# BUTTON-LEDs.net
KiCad netlist of a schematic drawn in Altium Designer
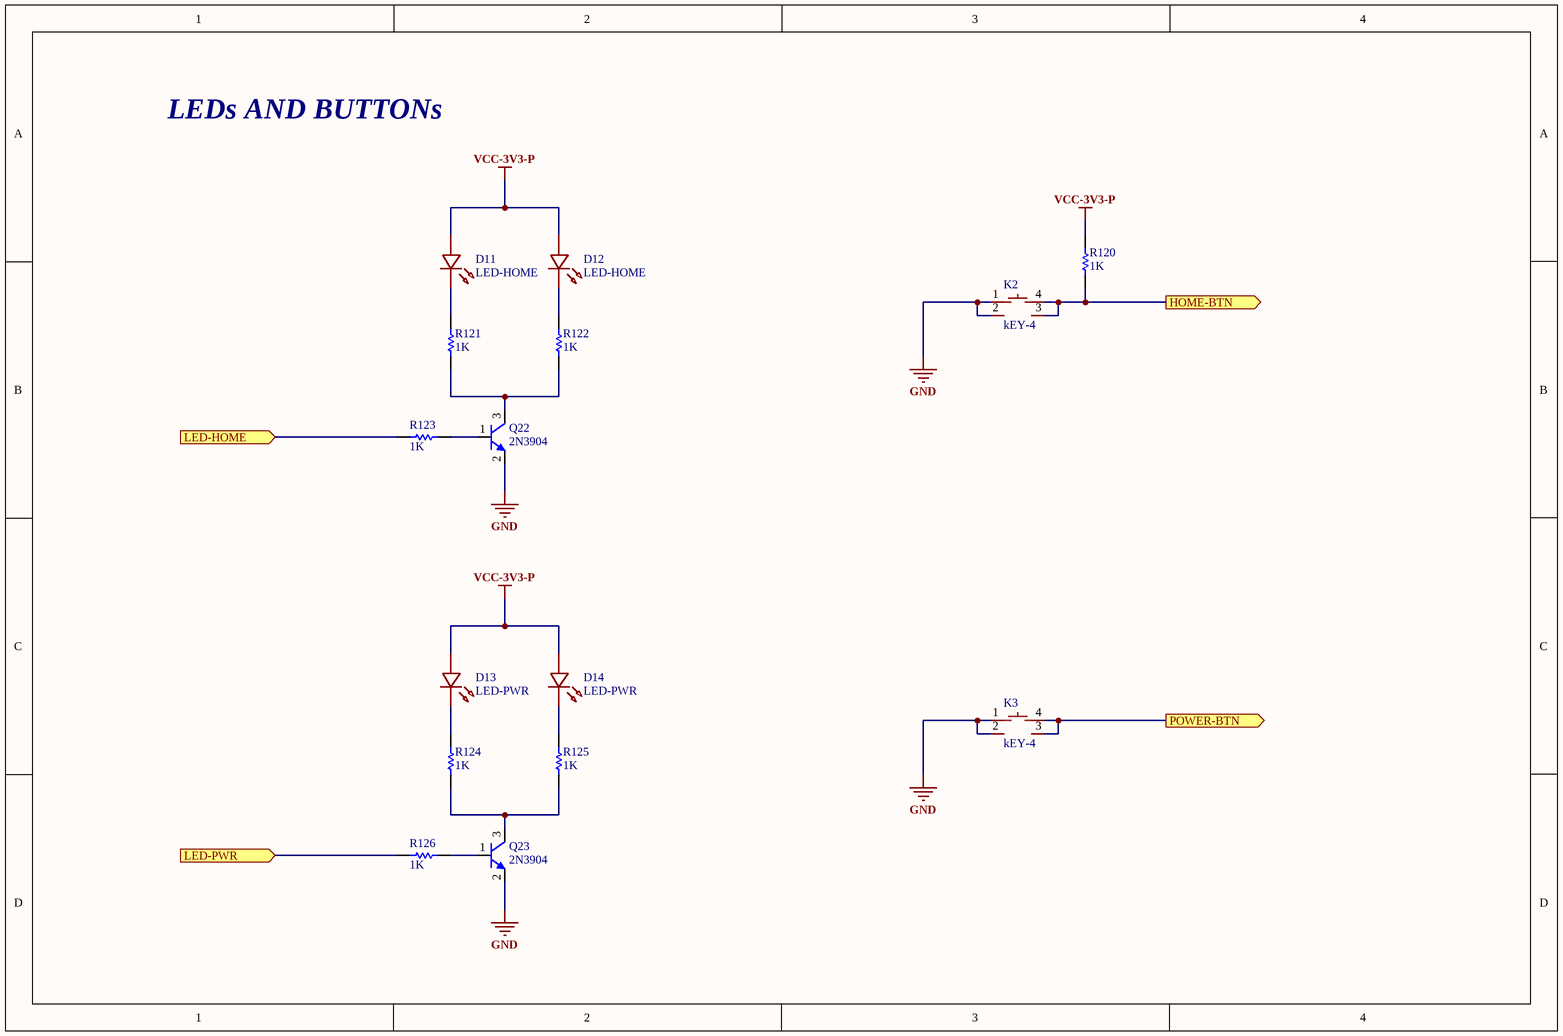
[diagram p0: BUTTON-LEDs .SchDoc]

(export (version "E")
  (design (tool "Eeschema 10.0.6"))
  (components
    (comp (ref "D11")
      (value "LED-HOME")
      (footprint "LED0603-B")
      (libsource (lib "DesignLibrary") (part "LED-SMD"))
    )
    (comp (ref "D12")
      (value "LED-HOME")
      (footprint "LED0603-B")
      (libsource (lib "DesignLibrary") (part "LED-SMD"))
    )
    (comp (ref "D13")
      (value "LED-PWR")
      (footprint "LED0603-B")
      (libsource (lib "DesignLibrary") (part "LED-SMD"))
    )
    (comp (ref "D14")
      (value "LED-PWR")
      (footprint "LED0603-B")
      (libsource (lib "DesignLibrary") (part "LED-SMD"))
    )
    (comp (ref "K2")
      (value "kEY-4")
      (footprint "KEY-SMD_4P-L6.0-W6.0-P4.50-LS9.0")
      (fields
        (field (name "MANUFACTURINGPARTNUMBER") "TS36CA-0.6 250gf 031")
        (field (name "MANUFACTURER") "SHOU HAN(首韩)")
      )
      (libsource (lib "DesignLibrary") (part "kEY-4"))
    )
    (comp (ref "K3")
      (value "kEY-4")
      (footprint "KEY-SMD_4P-L6.0-W6.0-P4.50-LS9.0")
      (fields
        (field (name "MANUFACTURINGPARTNUMBER") "TS36CA-0.6 250gf 031")
        (field (name "MANUFACTURER") "SHOU HAN(首韩)")
      )
      (libsource (lib "DesignLibrary") (part "kEY-4"))
    )
    (comp (ref "Q22")
      (value "2N3904")
      (footprint "SOT23-3D")
      (libsource (lib "DesignLibrary") (part "NPN-SOT23"))
    )
    (comp (ref "Q23")
      (value "2N3904")
      (footprint "SOT23-3D")
      (libsource (lib "DesignLibrary") (part "NPN-SOT23"))
    )
    (comp (ref "R120")
      (value "1K")
      (footprint "RES-0402")
      (libsource (lib "DesignLibrary") (part "Resistor-1"))
    )
    (comp (ref "R121")
      (value "1K")
      (footprint "RES-0402")
      (libsource (lib "DesignLibrary") (part "Resistor-1"))
    )
    (comp (ref "R122")
      (value "1K")
      (footprint "RES-0402")
      (libsource (lib "DesignLibrary") (part "Resistor-1"))
    )
    (comp (ref "R123")
      (value "1K")
      (footprint "RES-0402")
      (libsource (lib "DesignLibrary") (part "Resistor-1"))
    )
    (comp (ref "R124")
      (value "1K")
      (footprint "RES-0402")
      (libsource (lib "DesignLibrary") (part "Resistor-1"))
    )
    (comp (ref "R125")
      (value "1K")
      (footprint "RES-0402")
      (libsource (lib "DesignLibrary") (part "Resistor-1"))
    )
    (comp (ref "R126")
      (value "1K")
      (footprint "RES-0402")
      (libsource (lib "DesignLibrary") (part "Resistor-1"))
    )
  )
  (nets
    (net (code "1") (name "/HOME-BTN") (class "Default")
      (node (ref "K2") (pin "3") (pinfunction "3_3") (pintype "passive"))
      (node (ref "K2") (pin "4") (pinfunction "4_4") (pintype "passive"))
      (node (ref "R120") (pin "1") (pintype "passive"))
    )
    (net (code "2") (name "/LED-HOME") (class "Default") (node (ref "R123") (pin "2") (pintype "passive")))
    (net (code "3") (name "/LED-PWR") (class "Default") (node (ref "R126") (pin "2") (pintype "passive")))
    (net (code "4") (name "/POWER-BTN") (class "Default")
      (node (ref "K3") (pin "3") (pinfunction "3_3") (pintype "passive"))
      (node (ref "K3") (pin "4") (pinfunction "4_4") (pintype "passive"))
    )
    (net (code "5") (name "GND") (class "Default")
      (node (ref "K2") (pin "1") (pinfunction "1_1") (pintype "passive"))
      (node (ref "K2") (pin "2") (pinfunction "2_2") (pintype "passive"))
      (node (ref "K3") (pin "1") (pinfunction "1_1") (pintype "passive"))
      (node (ref "K3") (pin "2") (pinfunction "2_2") (pintype "passive"))
      (node (ref "Q22") (pin "2") (pinfunction "E_2") (pintype "passive"))
      (node (ref "Q23") (pin "2") (pinfunction "E_2") (pintype "passive"))
    )
    (net (code "6") (name "Net-(D11-Pad2)") (class "Default")
      (node (ref "D11") (pin "2") (pinfunction "2_2") (pintype "passive"))
      (node (ref "R121") (pin "2") (pintype "passive"))
    )
    (net (code "7") (name "Net-(D12-Pad2)") (class "Default")
      (node (ref "D12") (pin "2") (pinfunction "2_2") (pintype "passive"))
      (node (ref "R122") (pin "2") (pintype "passive"))
    )
    (net (code "8") (name "Net-(D13-Pad2)") (class "Default")
      (node (ref "D13") (pin "2") (pinfunction "2_2") (pintype "passive"))
      (node (ref "R124") (pin "2") (pintype "passive"))
    )
    (net (code "9") (name "Net-(D14-Pad2)") (class "Default")
      (node (ref "D14") (pin "2") (pinfunction "2_2") (pintype "passive"))
      (node (ref "R125") (pin "2") (pintype "passive"))
    )
    (net (code "10") (name "Net-(Q22-B)") (class "Default")
      (node (ref "Q22") (pin "1") (pinfunction "B_1") (pintype "passive"))
      (node (ref "R123") (pin "1") (pintype "passive"))
    )
    (net (code "11") (name "Net-(Q22-C)") (class "Default")
      (node (ref "Q22") (pin "3") (pinfunction "C_3") (pintype "passive"))
      (node (ref "R121") (pin "1") (pintype "passive"))
      (node (ref "R122") (pin "1") (pintype "passive"))
    )
    (net (code "12") (name "Net-(Q23-B)") (class "Default")
      (node (ref "Q23") (pin "1") (pinfunction "B_1") (pintype "passive"))
      (node (ref "R126") (pin "1") (pintype "passive"))
    )
    (net (code "13") (name "Net-(Q23-C)") (class "Default")
      (node (ref "Q23") (pin "3") (pinfunction "C_3") (pintype "passive"))
      (node (ref "R124") (pin "1") (pintype "passive"))
      (node (ref "R125") (pin "1") (pintype "passive"))
    )
    (net (code "14") (name "VCC-3V3-P") (class "Default")
      (node (ref "D11") (pin "1") (pinfunction "1_1") (pintype "passive"))
      (node (ref "D12") (pin "1") (pinfunction "1_1") (pintype "passive"))
      (node (ref "D13") (pin "1") (pinfunction "1_1") (pintype "passive"))
      (node (ref "D14") (pin "1") (pinfunction "1_1") (pintype "passive"))
      (node (ref "R120") (pin "2") (pintype "passive"))
    )
  )
)
